# Power.net
KiCad netlist of a schematic drawn in Altium Designer
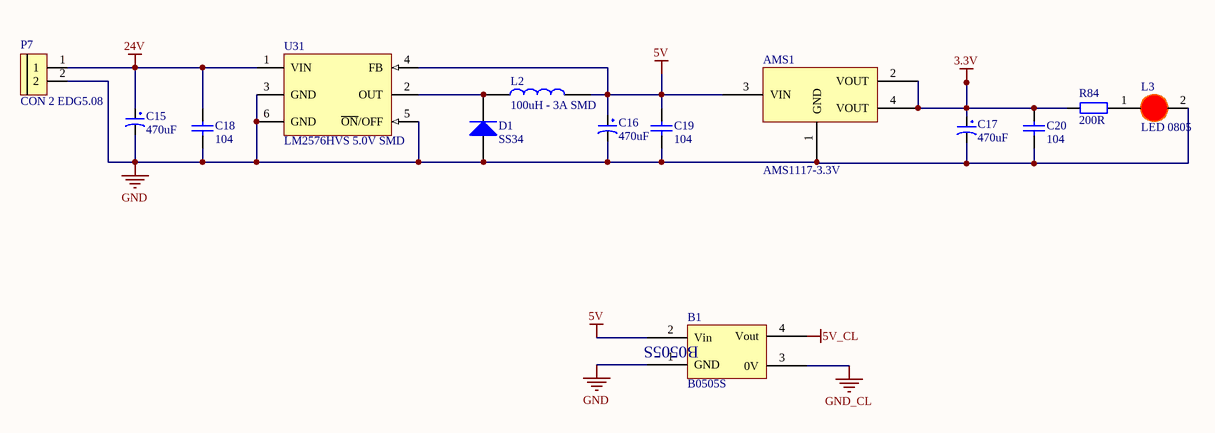
[diagram p0: Power.SchDoc]

(export (version "E")
  (design (tool "Eeschema 10.0.6"))
  (components
    (comp (ref "AMS1")
      (value "AMS1117-3.3V")
      (footprint "SOT223")
      (description "Dán")
      (libsource (lib "Altium_Lib_by_KhueNguyenCreator") (part "AMS1117 SMD"))
    )
    (comp (ref "B1")
      (value "B0505S")
      (footprint "B0505S")
      (description "Cắm")
      (libsource (lib "Altium_Lib_by_KhueNguyenCreator") (part "B0505S"))
    )
    (comp (ref "C15")
      (value "470uF")
      (footprint "tu hoa 10mm")
      (description "Cắm")
      (libsource (lib "Altium_Lib_by_KhueNguyenCreator") (part "Tu Hoa 470uF 50V 10x17"))
    )
    (comp (ref "C16")
      (value "470uF")
      (footprint "tu hoa 8mm")
      (description "Cắm")
      (libsource (lib "Altium_Lib_by_KhueNguyenCreator") (part "Tu Hoa 470uF 16V 8x11"))
    )
    (comp (ref "C17")
      (value "470uF")
      (footprint "tu hoa 8mm")
      (description "Cắm")
      (libsource (lib "Altium_Lib_by_KhueNguyenCreator") (part "Tu Hoa 470uF 16V 8x11"))
    )
    (comp (ref "C18")
      (value "104")
      (footprint "tu 0805")
      (description "Dán")
      (libsource (lib "Altium_Lib_by_KhueNguyenCreator") (part "Tu 0805 104 50V 10%"))
    )
    (comp (ref "C19")
      (value "104")
      (footprint "tu 0805")
      (description "Dán")
      (libsource (lib "Altium_Lib_by_KhueNguyenCreator") (part "Tu 0805 104 50V 10%"))
    )
    (comp (ref "C20")
      (value "104")
      (footprint "tu 0805")
      (description "Dán")
      (libsource (lib "Altium_Lib_by_KhueNguyenCreator") (part "Tu 0805 104 50V 10%"))
    )
    (comp (ref "D1")
      (value "SS34")
      (footprint "DIODE SMA")
      (description "Dán")
      (libsource (lib "Altium_Lib_by_KhueNguyenCreator") (part "Diode SS34 ( 1N5822 )"))
    )
    (comp (ref "L2")
      (value "100uH - 3A SMD")
      (footprint "Cuon Cam 12x12x10")
      (description "Dán")
      (libsource (lib "Altium_Lib_by_KhueNguyenCreator") (part "CUON CAM 100uH SMD"))
    )
    (comp (ref "L3")
      (value "LED 0805")
      (footprint "LED-0805-Red")
      (description "Dán")
      (libsource (lib "Altium_Lib_by_KhueNguyenCreator") (part "LED 0805 Do"))
    )
    (comp (ref "P7")
      (value "CON 2 EDG5.08")
      (footprint "CON 2 2EDG5.08")
      (description "Cắm")
      (libsource (lib "Altium_Lib_by_KhueNguyenCreator") (part "CON 2 EDG5.08"))
    )
    (comp (ref "R84")
      (value "200R")
      (footprint "tro smd 0805")
      (description "Dán")
      (libsource (lib "Altium_Lib_by_KhueNguyenCreator") (part "Tro 0805 5% 200R"))
    )
    (comp (ref "U31")
      (value "LM2576HVS 5.0V SMD")
      (footprint "TO263-5")
      (description "Dán")
      (libsource (lib "Altium_Lib_by_KhueNguyenCreator") (part "LM2576HVS 5.0V SMD"))
    )
  )
  (nets
    (net (code "1") (name "3.3V") (class "Default")
      (node (ref "AMS1") (pin "2") (pinfunction "VOUT_2") (pintype "passive"))
      (node (ref "AMS1") (pin "4") (pinfunction "VOUT_4") (pintype "passive"))
      (node (ref "C17") (pin "1") (pinfunction "1_1") (pintype "passive"))
      (node (ref "C20") (pin "1") (pinfunction "1_1") (pintype "passive"))
      (node (ref "R84") (pin "1") (pinfunction "1_1") (pintype "passive"))
    )
    (net (code "2") (name "5V") (class "Default")
      (node (ref "AMS1") (pin "3") (pinfunction "VIN_3") (pintype "passive"))
      (node (ref "B1") (pin "2") (pinfunction "Vin_2") (pintype "passive"))
      (node (ref "C16") (pin "1") (pinfunction "1_1") (pintype "passive"))
      (node (ref "C19") (pin "1") (pinfunction "1_1") (pintype "passive"))
      (node (ref "L2") (pin "2") (pinfunction "2_2") (pintype "passive"))
      (node (ref "U31") (pin "4") (pinfunction "FB_4") (pintype "input"))
    )
    (net (code "3") (name "5V_CL") (class "Default")
      (node (ref "B1") (pin "4") (pinfunction "Vout_4") (pintype "passive"))
    )
    (net (code "4") (name "24V") (class "Default")
      (node (ref "C15") (pin "1") (pinfunction "1_1") (pintype "passive"))
      (node (ref "C18") (pin "1") (pinfunction "1_1") (pintype "passive"))
      (node (ref "P7") (pin "1") (pinfunction "1_1") (pintype "passive"))
      (node (ref "U31") (pin "1") (pinfunction "VIN_1") (pintype "power_in"))
    )
    (net (code "5") (name "GND") (class "Default")
      (node (ref "AMS1") (pin "1") (pinfunction "GND_1") (pintype "passive"))
      (node (ref "B1") (pin "1") (pinfunction "GND_1") (pintype "passive"))
      (node (ref "C15") (pin "2") (pinfunction "2_2") (pintype "passive"))
      (node (ref "C16") (pin "2") (pinfunction "2_2") (pintype "passive"))
      (node (ref "C17") (pin "2") (pinfunction "2_2") (pintype "passive"))
      (node (ref "C18") (pin "2") (pinfunction "2_2") (pintype "passive"))
      (node (ref "C19") (pin "2") (pinfunction "2_2") (pintype "passive"))
      (node (ref "C20") (pin "2") (pinfunction "2_2") (pintype "passive"))
      (node (ref "D1") (pin "1") (pinfunction "A_1") (pintype "passive"))
      (node (ref "L3") (pin "2") (pinfunction "K_2") (pintype "passive"))
      (node (ref "P7") (pin "2") (pinfunction "2_2") (pintype "passive"))
      (node (ref "U31") (pin "3") (pinfunction "GND_3") (pintype "power_in"))
      (node (ref "U31") (pin "5") (pinfunction "~{ON}/OFF_5") (pintype "input"))
      (node (ref "U31") (pin "6") (pinfunction "GND_6") (pintype "passive"))
    )
    (net (code "6") (name "GND_CL") (class "Default")
      (node (ref "B1") (pin "3") (pinfunction "0V_3") (pintype "passive"))
    )
    (net (code "7") (name "Net-(D1-K)") (class "Default")
      (node (ref "D1") (pin "2") (pinfunction "K_2") (pintype "passive"))
      (node (ref "L2") (pin "1") (pinfunction "1_1") (pintype "passive"))
      (node (ref "U31") (pin "2") (pinfunction "OUT_2") (pintype "power_in"))
    )
    (net (code "8") (name "Net-(L3-A)") (class "Default")
      (node (ref "L3") (pin "1") (pinfunction "A_1") (pintype "passive"))
      (node (ref "R84") (pin "2") (pinfunction "2_2") (pintype "passive"))
    )
  )
)
